# bai_1.net
KiCad netlist of a schematic drawn in Altium Designer
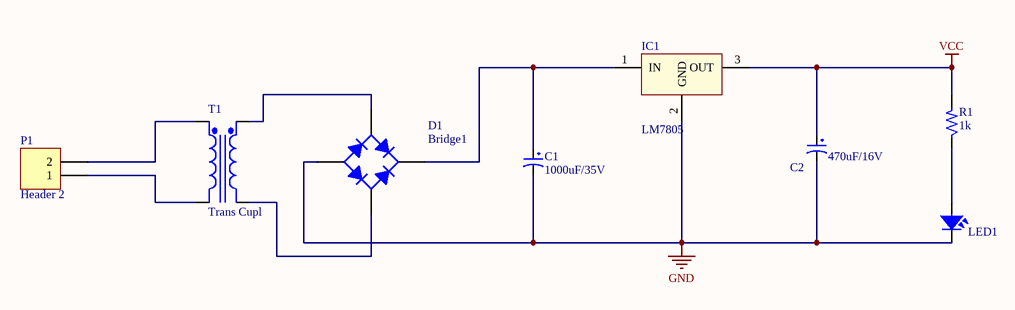
[diagram p0: bai 1.SchDoc]

(export (version "E")
  (design (tool "Eeschema 10.0.6"))
  (components
    (comp (ref "C1")
      (value "1000uF/35V")
      (footprint "CP4/8.5")
      (description "Cap 4700uF/50V")
      (libsource (lib "syhaunguyen") (part "CP7"))
    )
    (comp (ref "C2")
      (value "470uF/16V")
      (footprint "CP4/8.5")
      (description "Cap 4700uF/50V")
      (libsource (lib "syhaunguyen") (part "CP7"))
    )
    (comp (ref "D1")
      (value "Bridge1")
      (footprint "D-38")
      (description "Full Wave Diode Bridge")
      (fields (field (name "PUBLISHER") "Altium Limited"))
      (libsource (lib "Miscellaneous Devices") (part "Bridge1"))
    )
    (comp (ref "IC1")
      (value "LM7805")
      (footprint "QTO-220")
      (description "On ap +, from + 5 to + 24VDC")
      (libsource (lib "syhaunguyen") (part "LM78xx"))
    )
    (comp (ref "LED1")
      (value "LED")
      (footprint "LED-3")
      (description "LED Single colour Green and Red")
      (libsource (lib "syhaunguyen") (part "LED"))
    )
    (comp (ref "P1")
      (value "Header 2")
      (footprint "HDR1X2")
      (description "Header, 2-Pin")
      (fields (field (name "PUBLISHER") "Altium Limited"))
      (libsource (lib "Miscellaneous Connectors") (part "Header 2"))
    )
    (comp (ref "R1")
      (value "1k")
      (footprint "SM-RES-1206")
      (description "Resistor 1/4W")
      (libsource (lib "syhaunguyen") (part "R"))
    )
    (comp (ref "T1")
      (value "Trans Cupl")
      (footprint "TRF_4")
      (description "Transformer (Coupled Inductor Model)")
      (fields (field (name "PUBLISHER") "Altium Limited"))
      (libsource (lib "Miscellaneous Devices") (part "Trans Cupl"))
    )
  )
  (nets
    (net (code "1") (name "GND") (class "Default")
      (node (ref "C1") (pin "2") (pinfunction "2_2") (pintype "passive"))
      (node (ref "C2") (pin "2") (pinfunction "2_2") (pintype "passive"))
      (node (ref "D1") (pin "3") (pinfunction "A_3") (pintype "passive"))
      (node (ref "IC1") (pin "2") (pinfunction "GND_2") (pintype "passive"))
      (node (ref "LED1") (pin "2") (pinfunction "2_2") (pintype "passive"))
    )
    (net (code "2") (name "Net-(D1-K)") (class "Default")
      (node (ref "C1") (pin "1") (pinfunction "1_1") (pintype "passive"))
      (node (ref "D1") (pin "1") (pinfunction "K_1") (pintype "passive"))
      (node (ref "IC1") (pin "1") (pinfunction "IN_1") (pintype "passive"))
    )
    (net (code "3") (name "Net-(LED1-Pad1)") (class "Default")
      (node (ref "LED1") (pin "1") (pinfunction "1_1") (pintype "passive"))
      (node (ref "R1") (pin "1") (pinfunction "1_1") (pintype "passive"))
    )
    (net (code "4") (name "Net-(T1-Pri+)") (class "Default")
      (node (ref "P1") (pin "2") (pinfunction "2_2") (pintype "passive"))
      (node (ref "T1") (pin "1") (pinfunction "Pri+_1") (pintype "passive"))
    )
    (net (code "5") (name "Net-(T1-Pri-)") (class "Default")
      (node (ref "P1") (pin "1") (pinfunction "1_1") (pintype "passive"))
      (node (ref "T1") (pin "2") (pinfunction "Pri-_2") (pintype "passive"))
    )
    (net (code "6") (name "Net-(T1-Sec+)") (class "Default")
      (node (ref "D1") (pin "4") (pinfunction "C_4") (pintype "passive"))
      (node (ref "T1") (pin "3") (pinfunction "Sec+_3") (pintype "passive"))
    )
    (net (code "7") (name "Net-(T1-Sec-)") (class "Default")
      (node (ref "D1") (pin "2") (pinfunction "C_2") (pintype "passive"))
      (node (ref "T1") (pin "4") (pinfunction "Sec-_4") (pintype "passive"))
    )
    (net (code "8") (name "VCC") (class "Default")
      (node (ref "C2") (pin "1") (pinfunction "1_1") (pintype "passive"))
      (node (ref "IC1") (pin "3") (pinfunction "OUT_3") (pintype "passive"))
      (node (ref "R1") (pin "2") (pinfunction "2_2") (pintype "passive"))
    )
  )
)
